# Ada_-_Sensor_-_issue_4_0.net
KiCad netlist of a schematic drawn in Altium Designer
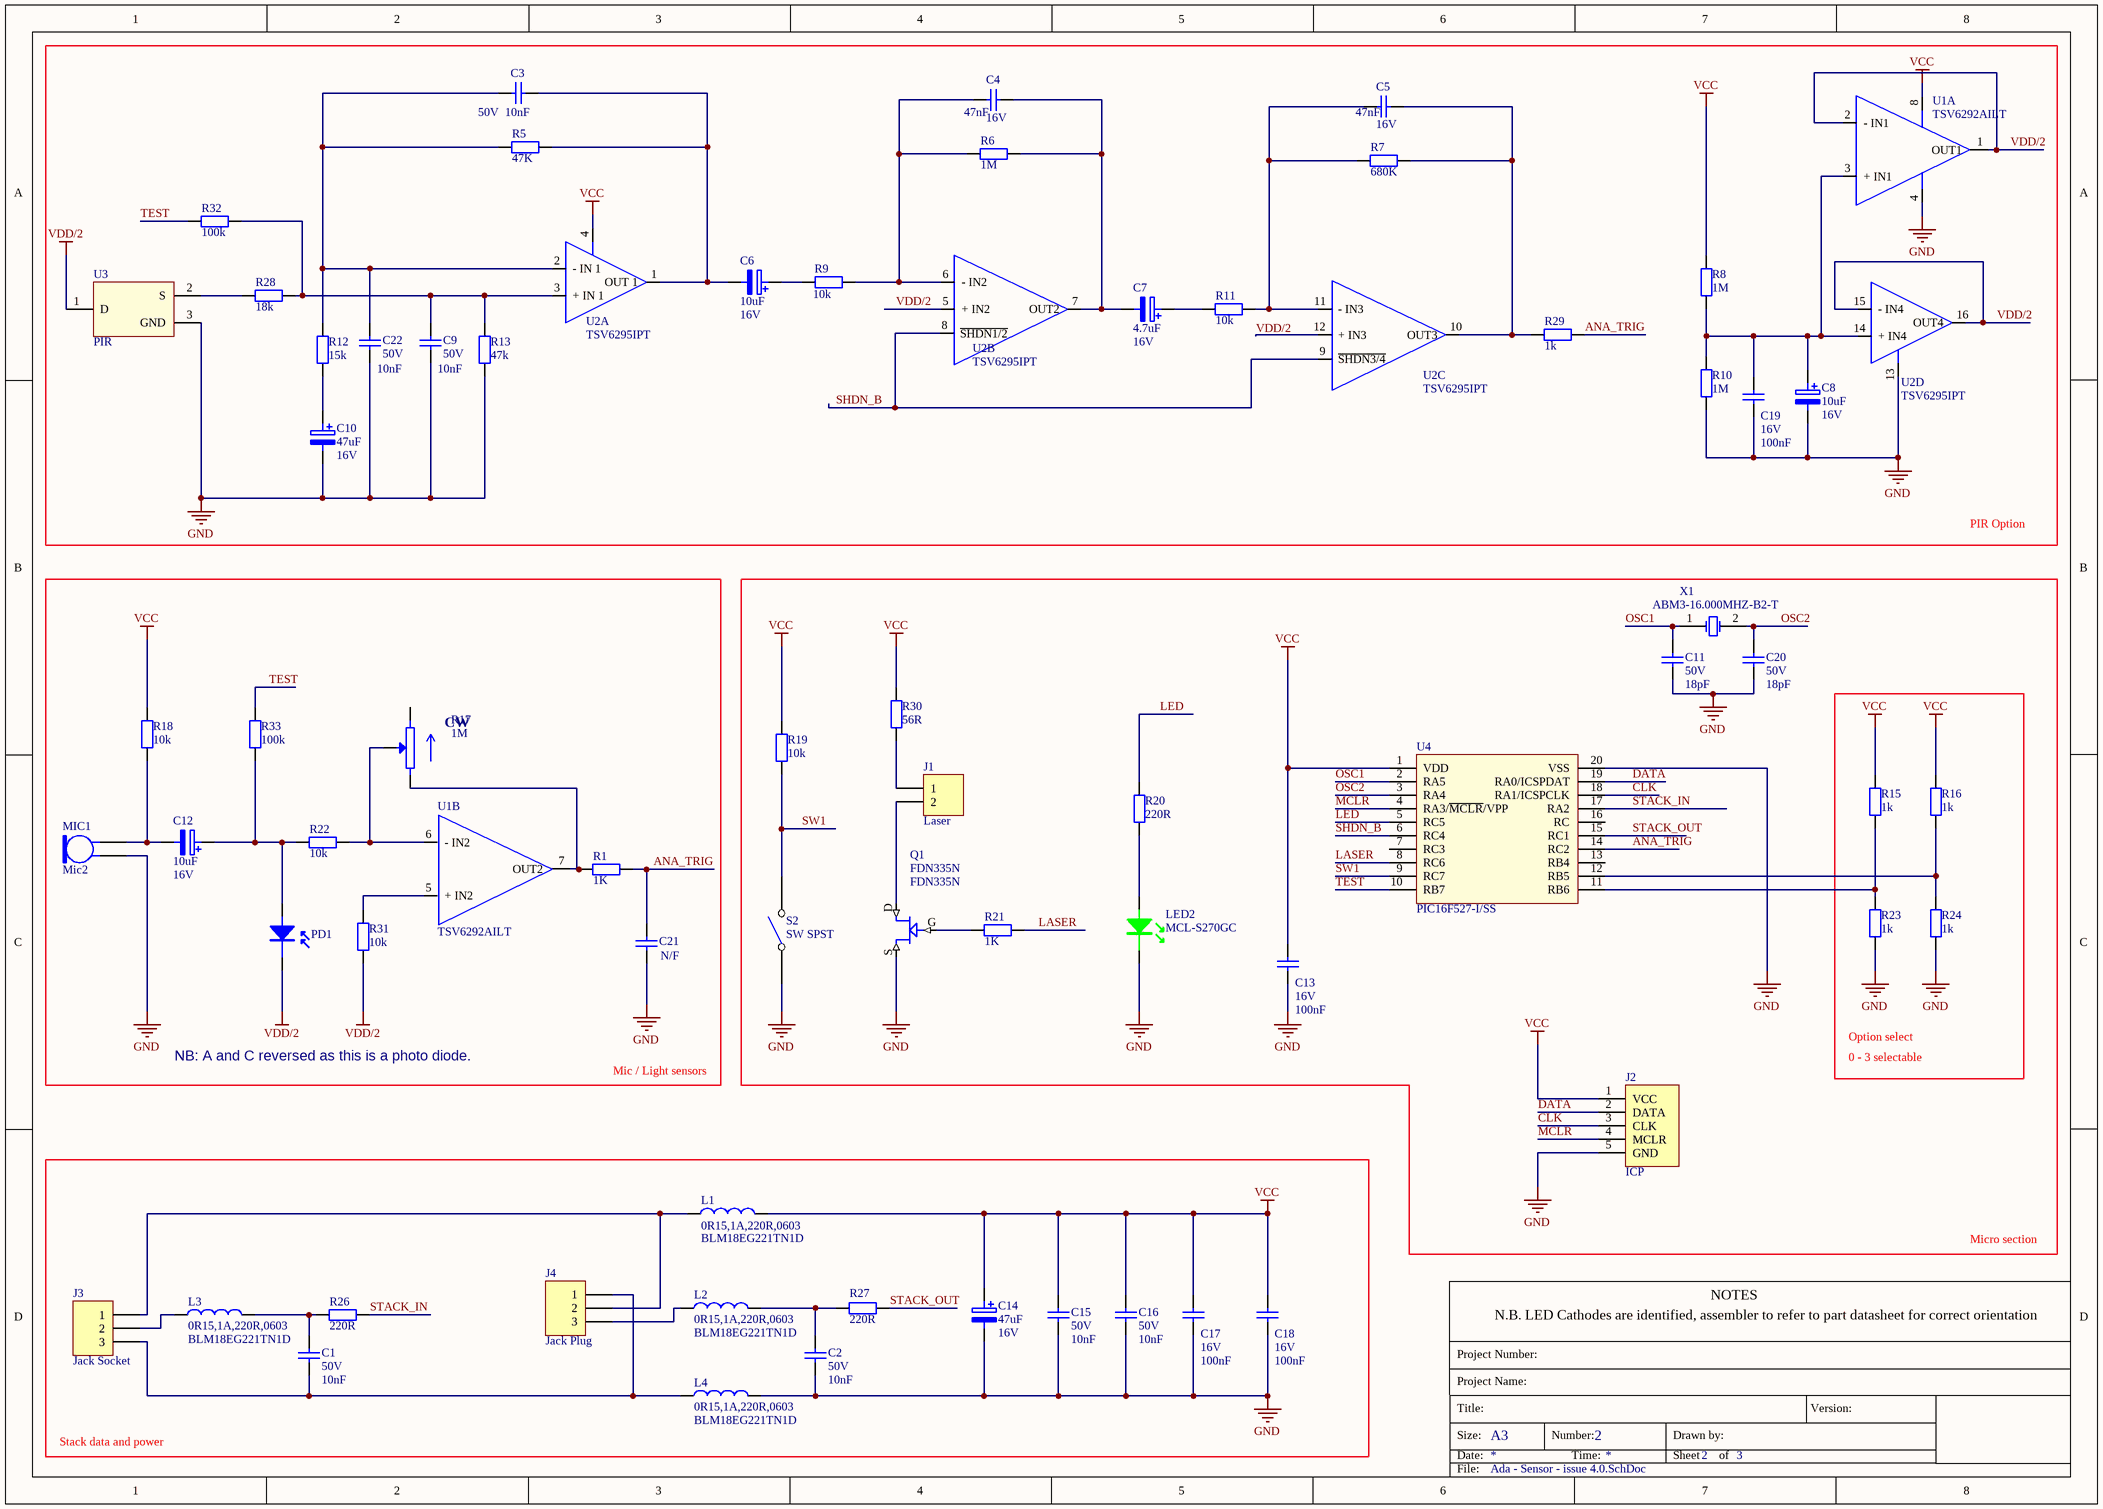
[diagram p0: Ada - Sensor - issue 4.0.SchDoc]

(export (version "E")
  (design (tool "Eeschema 10.0.6"))
  (components
    (comp (ref "C1")
      (value "10nF")
      (footprint "C0603")
      (description "Ceramic")
      (fields
        (field (name "MANUFACTURER") "MULTICOMP")
        (field (name "MANUF PART #") "MCCA000238")
        (field (name "VOLTAGE") "50V")
      )
      (libsource (lib "Capacitors") (part "10nF, 50V, 0603"))
    )
    (comp (ref "C2")
      (value "10nF")
      (footprint "C0603")
      (description "Ceramic")
      (fields
        (field (name "MANUFACTURER") "MULTICOMP")
        (field (name "MANUF PART #") "MCCA000238")
        (field (name "VOLTAGE") "50V")
      )
      (libsource (lib "Capacitors") (part "10nF, 50V, 0603"))
    )
    (comp (ref "C3")
      (value "10nF")
      (footprint "C0603")
      (description "Ceramic")
      (fields
        (field (name "MANUFACTURER") "MULTICOMP")
        (field (name "MANUF PART #") "MCCA000238")
        (field (name "VOLTAGE") "50V")
      )
      (libsource (lib "Passives Rev B") (part "Capacitor 0805"))
    )
    (comp (ref "C4")
      (value "47nF")
      (footprint "C0603")
      (description "Ceramic")
      (fields
        (field (name "MANUFACTURER") "YAGEO")
        (field (name "MANUF PART #") "CC0603KRX7R7BB473")
        (field (name "VOLTAGE") "16V")
      )
      (libsource (lib "Passives Rev B") (part "Capacitor 0603"))
    )
    (comp (ref "C5")
      (value "47nF")
      (footprint "C0603")
      (description "Ceramic")
      (fields
        (field (name "MANUFACTURER") "YAGEO")
        (field (name "MANUF PART #") "CC0603KRX7R7BB473")
        (field (name "VOLTAGE") "16V")
      )
      (libsource (lib "Passives Rev B") (part "Capacitor 0603"))
    )
    (comp (ref "C6")
      (value "10uF")
      (footprint "CASE_A")
      (description "ELECTROLYTIC")
      (fields
        (field (name "MANUFACTURER") "VISHAY SPRAGUE")
        (field (name "MANUF PART #") "293D106X9016A2TE3")
        (field (name "VOLTAGE") "16V")
      )
      (libsource (lib "Capacitors") (part "47uF, 25V, case D8"))
    )
    (comp (ref "C7")
      (value "4.7uF")
      (footprint "CASE_A")
      (description "TANT")
      (fields
        (field (name "MANUFACTURER") "VISHAY SPRAGUE")
        (field (name "MANUF PART #") "293D475X9016A2TE3")
        (field (name "VOLTAGE") "16V")
      )
      (libsource (lib "Capacitors") (part "47uF, 25V, case D8"))
    )
    (comp (ref "C8")
      (value "10uF")
      (footprint "CASE_A")
      (description "ELECTROLYTIC")
      (fields
        (field (name "MANUFACTURER") "VISHAY SPRAGUE")
        (field (name "MANUF PART #") "293D106X9016A2TE3")
        (field (name "VOLTAGE") "16V")
      )
      (libsource (lib "Capacitors") (part "47uF, 25V, case D8"))
    )
    (comp (ref "C9")
      (value "10nF")
      (footprint "C0603")
      (description "Ceramic")
      (fields
        (field (name "MANUFACTURER") "MULTICOMP")
        (field (name "MANUF PART #") "MCCA000238")
        (field (name "VOLTAGE") "50V")
      )
      (libsource (lib "Passives Rev B") (part "Capacitor 0805"))
    )
    (comp (ref "C10")
      (value "47uF")
      (footprint "CAP6.8/6.8")
      (description "ELECTROLYTIC")
      (fields
        (field (name "MANUFACTURER") "NICHICON")
        (field (name "MANUF PART #") "UUT1C470MCL1GS")
        (field (name "VOLTAGE") "16V")
      )
      (libsource (lib "Capacitors") (part "47uF, 25V, case D8"))
    )
    (comp (ref "C11")
      (value "18pF")
      (footprint "C0603")
      (description "Ceramic")
      (fields
        (field (name "MANUFACTURER") "KEMET")
        (field (name "MANUF PART #") "C0603C180J5GAC")
        (field (name "VOLTAGE") "50V")
      )
      (libsource (lib "Capacitors") (part "18pF, 50V, 0603"))
    )
    (comp (ref "C12")
      (value "10uF")
      (footprint "CASE_A")
      (description "ELECTROLYTIC")
      (fields
        (field (name "MANUFACTURER") "VISHAY SPRAGUE")
        (field (name "MANUF PART #") "293D106X9016A2TE3")
        (field (name "VOLTAGE") "16V")
      )
      (libsource (lib "Capacitors") (part "47uF, 25V, case D8"))
    )
    (comp (ref "C13")
      (value "100nF")
      (footprint "C0603")
      (description "Ceramic")
      (fields
        (field (name "MANUFACTURER") "TruCap")
        (field (name "MANUF PART #") "B0603R104")
        (field (name "VOLTAGE") "16V")
      )
      (libsource (lib "Capacitors") (part "100nF, 16V, 0603"))
    )
    (comp (ref "C14")
      (value "47uF")
      (footprint "CAP6.8/6.8")
      (description "ELECTROLYTIC")
      (fields
        (field (name "MANUFACTURER") "NICHICON")
        (field (name "MANUF PART #") "UUT1C470MCL1GS")
        (field (name "VOLTAGE") "16V")
      )
      (libsource (lib "Capacitors") (part "47uF, 25V, case D8"))
    )
    (comp (ref "C15")
      (value "10nF")
      (footprint "C0603")
      (description "Ceramic")
      (fields
        (field (name "MANUFACTURER") "MULTICOMP")
        (field (name "MANUF PART #") "MCCA000238")
        (field (name "VOLTAGE") "50V")
      )
      (libsource (lib "Capacitors") (part "10nF, 50V, 0603"))
    )
    (comp (ref "C16")
      (value "10nF")
      (footprint "C0603")
      (description "Ceramic")
      (fields
        (field (name "MANUFACTURER") "MULTICOMP")
        (field (name "MANUF PART #") "MCCA000238")
        (field (name "VOLTAGE") "50V")
      )
      (libsource (lib "Capacitors") (part "10nF, 50V, 0603"))
    )
    (comp (ref "C17")
      (value "100nF")
      (footprint "C0603")
      (description "Ceramic")
      (fields
        (field (name "MANUFACTURER") "TruCap")
        (field (name "MANUF PART #") "B0603R104")
        (field (name "VOLTAGE") "16V")
      )
      (libsource (lib "Capacitors") (part "100nF, 16V, 0603"))
    )
    (comp (ref "C18")
      (value "100nF")
      (footprint "C0603")
      (description "Ceramic")
      (fields
        (field (name "MANUFACTURER") "TruCap")
        (field (name "MANUF PART #") "B0603R104")
        (field (name "VOLTAGE") "16V")
      )
      (libsource (lib "Capacitors") (part "100nF, 16V, 0603"))
    )
    (comp (ref "C19")
      (value "100nF")
      (footprint "C0603")
      (description "Ceramic")
      (fields
        (field (name "MANUFACTURER") "TruCap")
        (field (name "MANUF PART #") "B0603R104")
        (field (name "VOLTAGE") "16V")
      )
      (libsource (lib "Capacitors") (part "100nF, 16V, 0603"))
    )
    (comp (ref "C20")
      (value "18pF")
      (footprint "C0603")
      (description "Ceramic")
      (fields
        (field (name "MANUFACTURER") "KEMET")
        (field (name "MANUF PART #") "C0603C180J5GAC")
        (field (name "VOLTAGE") "50V")
      )
      (libsource (lib "Capacitors") (part "18pF, 50V, 0603"))
    )
    (comp (ref "C21")
      (value "N/F")
      (footprint "C0603")
      (description "Ceramic")
      (fields (field (name "Comment") "Capacitor 0603"))
      (libsource (lib "Passives Rev B") (part "Capacitor 0603"))
    )
    (comp (ref "C22")
      (value "10nF")
      (footprint "C0603")
      (description "Ceramic")
      (fields
        (field (name "MANUFACTURER") "MULTICOMP")
        (field (name "MANUF PART #") "MCCA000238")
        (field (name "VOLTAGE") "50V")
      )
      (libsource (lib "Passives Rev B") (part "Capacitor 0805"))
    )
    (comp (ref "J1")
      (value "Laser")
      (footprint "SIP2")
      (description "Header, 2-Pin")
      (libsource (lib "Connectors") (part "Header 2"))
    )
    (comp (ref "J2")
      (value "ICP")
      (footprint "ICP")
      (description "PIC IN CIRCUIT PROGRAMMING HEADER")
      (fields (field (name "MANUFACTURER") "TruConnect") (field (name "MANUF PART #") "22-0510"))
      (libsource (lib "Connectors") (part "ICP"))
    )
    (comp (ref "J3")
      (value "Jack Socket")
      (footprint "sip3")
      (description "Header, 3-Pin")
      (libsource (lib "Connectors") (part "Header 3"))
    )
    (comp (ref "J4")
      (value "Jack Plug")
      (footprint "3 way sip RA")
      (description "Header, 3-Pin")
      (libsource (lib "Connectors") (part "Header 3"))
    )
    (comp (ref "L1")
      (value "0R15,1A,220R,0603")
      (footprint "L0603")
      (description "FERRITE BEAD")
      (fields
        (field (name "MANUFACTURER") "MURATA")
        (field (name "MANUF PART #") "BLM18EG221TN1D")
        (field (name "ALTIUM_VALUE") "BLM18EG221TN1D")
      )
      (libsource (lib "Inductors") (part "0R15,1A,220R,0603"))
    )
    (comp (ref "L2")
      (value "0R15,1A,220R,0603")
      (footprint "L0603")
      (description "FERRITE BEAD")
      (fields
        (field (name "MANUFACTURER") "MURATA")
        (field (name "MANUF PART #") "BLM18EG221TN1D")
        (field (name "ALTIUM_VALUE") "BLM18EG221TN1D")
      )
      (libsource (lib "Inductors") (part "0R15,1A,220R,0603"))
    )
    (comp (ref "L3")
      (value "0R15,1A,220R,0603")
      (footprint "L0603")
      (description "FERRITE BEAD")
      (fields
        (field (name "MANUFACTURER") "MURATA")
        (field (name "MANUF PART #") "BLM18EG221TN1D")
        (field (name "ALTIUM_VALUE") "BLM18EG221TN1D")
      )
      (libsource (lib "Inductors") (part "0R15,1A,220R,0603"))
    )
    (comp (ref "L4")
      (value "0R15,1A,220R,0603")
      (footprint "L0603")
      (description "FERRITE BEAD")
      (fields
        (field (name "MANUFACTURER") "MURATA")
        (field (name "MANUF PART #") "BLM18EG221TN1D")
        (field (name "ALTIUM_VALUE") "BLM18EG221TN1D")
      )
      (libsource (lib "Inductors") (part "0R15,1A,220R,0603"))
    )
    (comp (ref "LED2")
      (value "MCL-S270GC")
      (footprint "LED, GREEN, 0805")
      (description "MULTICOMP")
      (fields (field (name "PART NO.") "1581242") (field (name "Comment") "LED GREEN 0805"))
      (libsource (lib "Diodes") (part "LED GREEN 0805"))
    )
    (comp (ref "MIC1")
      (value "Mic2")
      (footprint "ECM")
      (description "PROJECTS UNLIMITED - AOM-4542P-R - MICROPHONE, OMNI PCB, 9.7MM")
      (fields (field (name "MANUFACTURER") "PROJECTS UNLIMITED") (field (name "MANUF PART #") "AOM-4542P-R"))
      (libsource (lib "General") (part "Mic2"))
    )
    (comp (ref "PD1")
      (value "PHOTODIODE")
      (footprint "DOME LENS")
      (description "DIODE, PIN, SMD, DOME LENS")
      (fields (field (name "MANUFACTURER") "VISHAY") (field (name "MANUF PART #") "VEMD2520X01"))
      (libsource (lib "ECO001_LIB") (part "PHOTODIODE"))
    )
    (comp (ref "Q1")
      (value "FDN335N")
      (footprint "SOT-23")
      (fields
        (field (name "MANUFACTURER") "FAIRCHILD SEMICONDUCTOR")
        (field (name "PART NO.") "9845348RL")
        (field (name "ALTIUM_VALUE") "FDN335N")
      )
      (libsource (lib "Transistors and FETs") (part "FDN335N"))
    )
    (comp (ref "R1")
      (value "1K")
      (footprint "R0603")
      (description "Resistor 0603")
      (libsource (lib "") (part "Resistor 0603_3"))
    )
    (comp (ref "R5")
      (value "47K")
      (footprint "R0603")
      (description "Resistor 0603")
      (libsource (lib "") (part "Resistor 0603_1"))
    )
    (comp (ref "R6")
      (value "1M")
      (footprint "R0603")
      (description "Resistor 0603")
      (libsource (lib "") (part "Resistor 0603_3"))
    )
    (comp (ref "R7")
      (value "680K")
      (footprint "R0603")
      (description "Resistor 0603")
      (libsource (lib "") (part "Resistor 0603_1"))
    )
    (comp (ref "R8")
      (value "1M")
      (footprint "R0603")
      (description "Resistor 0603")
      (libsource (lib "") (part "Resistor 0603_2"))
    )
    (comp (ref "R9")
      (value "10k")
      (footprint "R0603")
      (description "Resistor 0603")
      (libsource (lib "") (part "Resistor 0603_1"))
    )
    (comp (ref "R10")
      (value "1M")
      (footprint "R0603")
      (description "Resistor 0603")
      (libsource (lib "") (part "Resistor 0603_2"))
    )
    (comp (ref "R11")
      (value "10k")
      (footprint "R0603")
      (description "Resistor 0603")
      (libsource (lib "") (part "Resistor 0603_1"))
    )
    (comp (ref "R12")
      (value "15k")
      (footprint "R0603")
      (description "Resistor 0603")
      (libsource (lib "") (part "Resistor 0603_2"))
    )
    (comp (ref "R13")
      (value "47k")
      (footprint "R0603")
      (description "Resistor 0805")
      (libsource (lib "Passives Rev B") (part "Resistor 0805"))
    )
    (comp (ref "R15")
      (value "1k")
      (footprint "R0603")
      (description "Resistor 0603")
      (libsource (lib "") (part "Resistor 0603_2"))
    )
    (comp (ref "R16")
      (value "1k")
      (footprint "R0603")
      (description "Resistor 0603")
      (libsource (lib "") (part "Resistor 0603_2"))
    )
    (comp (ref "R17")
      (value "1M")
      (footprint "preset_Iskra square")
      (description "1m Pnz10za Preset Potentiometer")
      (fields (field (name "MANUFACTURER") "Iskra") (field (name "MANUF PART #") "PNZ10ZA 1M"))
      (libsource (lib "DEVICE") (part "POT2"))
    )
    (comp (ref "R18")
      (value "10k")
      (footprint "R0603")
      (description "Resistor 0603")
      (libsource (lib "") (part "Resistor 0603_3"))
    )
    (comp (ref "R19")
      (value "10k")
      (footprint "R0603")
      (description "Resistor 0603")
      (libsource (lib "") (part "Resistor 0603_2"))
    )
    (comp (ref "R20")
      (value "220R")
      (footprint "R0603")
      (description "Resistor 0603")
      (libsource (lib "") (part "Resistor 0603_2"))
    )
    (comp (ref "R21")
      (value "1K")
      (footprint "R0603")
      (description "Resistor 0603")
      (libsource (lib "") (part "Resistor 0603_1"))
    )
    (comp (ref "R22")
      (value "10k")
      (footprint "R0603")
      (description "Resistor 0603")
      (libsource (lib "Passives Rev B") (part "Resistor 0603"))
    )
    (comp (ref "R23")
      (value "1k")
      (footprint "R0603")
      (description "Resistor 0603")
      (libsource (lib "") (part "Resistor 0603_2"))
    )
    (comp (ref "R24")
      (value "1k")
      (footprint "R0603")
      (description "Resistor 0603")
      (libsource (lib "") (part "Resistor 0603_2"))
    )
    (comp (ref "R26")
      (value "220R")
      (footprint "R0603")
      (description "Resistor 0603")
      (libsource (lib "Passives Rev B") (part "Resistor 0603"))
    )
    (comp (ref "R27")
      (value "220R")
      (footprint "R0603")
      (description "Resistor 0603")
      (libsource (lib "Passives Rev B") (part "Resistor 0603"))
    )
    (comp (ref "R28")
      (value "18k")
      (footprint "R0603")
      (description "Resistor 0603")
      (libsource (lib "") (part "Resistor 0603_1"))
    )
    (comp (ref "R29")
      (value "1k")
      (footprint "R0603")
      (description "Resistor 0603")
      (libsource (lib "") (part "Resistor 0603_1"))
    )
    (comp (ref "R30")
      (value "56R")
      (footprint "R0603")
      (description "Resistor 0603")
      (libsource (lib "") (part "Resistor 0603_2"))
    )
    (comp (ref "R31")
      (value "10k")
      (footprint "R0603")
      (description "Resistor 0603")
      (libsource (lib "") (part "Resistor 0603_1"))
    )
    (comp (ref "R32")
      (value "100k")
      (footprint "R0603")
      (description "Resistor 0603")
      (libsource (lib "") (part "Resistor 0603_1"))
    )
    (comp (ref "R33")
      (value "100k")
      (footprint "R0603")
      (description "Resistor 0603")
      (libsource (lib "Passives Rev B") (part "Resistor 0603"))
    )
    (comp (ref "S2")
      (value "SW SPST")
      (footprint "MFP113D")
      (fields
        (field (name "MANUFACTURER") "KNITTER-SWITCH")
        (field (name "MANUF PART #") "MFP113D")
        (field (name "PART NO.") "702-3634")
      )
      (libsource (lib "Switches") (part "SW SPST"))
    )
    (comp (ref "U1")
      (value "TSV6292AILT")
      (footprint "SOT23 8 pin")
      (description "low power Op Amp")
      (fields (field (name "MANUFACTURER") "STMICROELECTRONICS") (field (name "PART NO.") "2067873"))
      (libsource (lib "TRI002_SCHLIB_1.3") (part "TSV6292AILT"))
    )
    (comp (ref "U2")
      (value "TSV6295IPT")
      (footprint "TSSOP16")
      (description "low power Op Amp")
      (fields (field (name "MANUFACTURER") "STMICROELECTRONICS") (field (name "PART NO.") "1842580"))
      (libsource (lib "ECO001_LIB") (part "TSV6295IPT"))
    )
    (comp (ref "U3")
      (value "PIR")
      (footprint "PIR_TO-5")
      (description "PIR detector")
      (fields (field (name "MANUFACTURER") "EXCELITAS TECH") (field (name "MANUF PART #") "LHI_968"))
      (libsource (lib "ECO001_LIB") (part "LHI_968"))
    )
    (comp (ref "U4")
      (value "PIC16F527-I/SS")
      (footprint "SSOP20")
      (description "8bit uProcessor")
      (fields (field (name "MANUFACTURER") "MICROCHIP") (field (name "PART NO.") "2301100"))
      (libsource (lib "TRI002 Sensor") (part "PIC16F527"))
    )
    (comp (ref "X1")
      (value "ABM3-16.000MHZ-B2-T")
      (footprint "ABS10")
      (description "CRYSTAL, 16MHZ, 18PF CL, 5X3.2MM, SMT")
      (fields (field (name "MANUFACTURER") "ABRACON") (field (name "PART NO.") "1611806"))
      (libsource (lib "General") (part "XTAL SMD 2pin"))
    )
  )
  (nets
    (net (code "1") (name "/ANA_TRIG") (class "Default")
      (node (ref "C21") (pin "2") (pinfunction "2_2") (pintype "passive"))
      (node (ref "R1") (pin "2") (pinfunction "2_2") (pintype "passive"))
      (node (ref "R29") (pin "1") (pinfunction "1_1") (pintype "passive"))
      (node (ref "U4") (pin "14") (pinfunction "RC2_14") (pintype "passive"))
    )
    (net (code "2") (name "/CLK") (class "Default")
      (node (ref "J2") (pin "3") (pinfunction "CLK_3") (pintype "passive"))
      (node (ref "U4") (pin "18") (pinfunction "RA1/ICSPCLK_18") (pintype "passive"))
    )
    (net (code "3") (name "/DATA") (class "Default")
      (node (ref "J2") (pin "2") (pinfunction "DATA_2") (pintype "passive"))
      (node (ref "U4") (pin "19") (pinfunction "RA0/ICSPDAT_19") (pintype "passive"))
    )
    (net (code "4") (name "/LASER") (class "Default")
      (node (ref "R21") (pin "1") (pinfunction "1_1") (pintype "passive"))
      (node (ref "U4") (pin "8") (pinfunction "RC6_8") (pintype "passive"))
    )
    (net (code "5") (name "/LED") (class "Default")
      (node (ref "R20") (pin "2") (pinfunction "2_2") (pintype "passive"))
      (node (ref "U4") (pin "5") (pinfunction "RC5_5") (pintype "passive"))
    )
    (net (code "6") (name "/MCLR") (class "Default")
      (node (ref "J2") (pin "4") (pinfunction "MCLR_4") (pintype "passive"))
      (node (ref "U4") (pin "4") (pinfunction "RA3/~{MCLR}/VPP_4") (pintype "passive"))
    )
    (net (code "7") (name "/OSC1") (class "Default")
      (node (ref "C11") (pin "2") (pinfunction "2_2") (pintype "passive"))
      (node (ref "U4") (pin "2") (pinfunction "RA5_2") (pintype "passive"))
      (node (ref "X1") (pin "1") (pinfunction "OSC1_1") (pintype "passive"))
    )
    (net (code "8") (name "/OSC2") (class "Default")
      (node (ref "C20") (pin "2") (pinfunction "2_2") (pintype "passive"))
      (node (ref "U4") (pin "3") (pinfunction "RA4_3") (pintype "passive"))
      (node (ref "X1") (pin "2") (pinfunction "OSC2_2") (pintype "passive"))
    )
    (net (code "9") (name "/SHDN_B") (class "Default")
      (node (ref "U2") (pin "8") (pinfunction "~{SHDN1/2}_8") (pintype "passive"))
      (node (ref "U2") (pin "9") (pinfunction "~{SHDN3/4}_9") (pintype "passive"))
      (node (ref "U4") (pin "6") (pinfunction "RC4_6") (pintype "passive"))
    )
    (net (code "10") (name "/STACK_IN") (class "Default")
      (node (ref "R26") (pin "1") (pinfunction "1_1") (pintype "passive"))
      (node (ref "U4") (pin "17") (pinfunction "RA2_17") (pintype "passive"))
    )
    (net (code "11") (name "/STACK_OUT") (class "Default")
      (node (ref "R27") (pin "1") (pinfunction "1_1") (pintype "passive"))
      (node (ref "U4") (pin "15") (pinfunction "RC1_15") (pintype "passive"))
    )
    (net (code "12") (name "/SW1") (class "Default")
      (node (ref "R19") (pin "1") (pinfunction "1_1") (pintype "passive"))
      (node (ref "S2") (pin "2") (pinfunction "NO_2") (pintype "passive"))
      (node (ref "U4") (pin "9") (pinfunction "RC7_9") (pintype "passive"))
    )
    (net (code "13") (name "/TEST") (class "Default")
      (node (ref "R32") (pin "2") (pinfunction "2_2") (pintype "passive"))
      (node (ref "R33") (pin "1") (pinfunction "1_1") (pintype "passive"))
      (node (ref "U4") (pin "10") (pinfunction "RB7_10") (pintype "passive"))
    )
    (net (code "14") (name "GND") (class "Default")
      (node (ref "C10") (pin "2") (pinfunction "2_2") (pintype "passive"))
      (node (ref "C11") (pin "1") (pinfunction "1_1") (pintype "passive"))
      (node (ref "C13") (pin "1") (pinfunction "1_1") (pintype "passive"))
      (node (ref "C14") (pin "2") (pinfunction "2_2") (pintype "passive"))
      (node (ref "C15") (pin "1") (pinfunction "1_1") (pintype "passive"))
      (node (ref "C16") (pin "1") (pinfunction "1_1") (pintype "passive"))
      (node (ref "C17") (pin "1") (pinfunction "1_1") (pintype "passive"))
      (node (ref "C18") (pin "1") (pinfunction "1_1") (pintype "passive"))
      (node (ref "C19") (pin "1") (pinfunction "1_1") (pintype "passive"))
      (node (ref "C2") (pin "1") (pinfunction "1_1") (pintype "passive"))
      (node (ref "C20") (pin "1") (pinfunction "1_1") (pintype "passive"))
      (node (ref "C21") (pin "1") (pinfunction "1_1") (pintype "passive"))
      (node (ref "C22") (pin "1") (pinfunction "1_1") (pintype "passive"))
      (node (ref "C8") (pin "2") (pinfunction "2_2") (pintype "passive"))
      (node (ref "C9") (pin "1") (pinfunction "1_1") (pintype "passive"))
      (node (ref "J2") (pin "5") (pinfunction "GND_5") (pintype "passive"))
      (node (ref "L4") (pin "2") (pinfunction "2_2") (pintype "passive"))
      (node (ref "LED2") (pin "K") (pinfunction "K_K") (pintype "passive"))
      (node (ref "MIC1") (pin "2") (pinfunction "2_2") (pintype "passive"))
      (node (ref "Q1") (pin "S") (pinfunction "S_S") (pintype "input"))
      (node (ref "R10") (pin "1") (pinfunction "1_1") (pintype "passive"))
      (node (ref "R13") (pin "2") (pinfunction "2_2") (pintype "passive"))
      (node (ref "R23") (pin "1") (pinfunction "1_1") (pintype "passive"))
      (node (ref "R24") (pin "1") (pinfunction "1_1") (pintype "passive"))
      (node (ref "S2") (pin "1") (pinfunction "COMMON_1") (pintype "passive"))
      (node (ref "U1") (pin "4") (pinfunction "V+_4") (pintype "passive"))
      (node (ref "U2") (pin "13") (pinfunction "V-_13") (pintype "passive"))
      (node (ref "U3") (pin "3") (pinfunction "GND_3") (pintype "passive"))
      (node (ref "U4") (pin "20") (pinfunction "VSS_20") (pintype "passive"))
    )
    (net (code "15") (name "Net-(C1-Pad1)") (class "Default")
      (node (ref "C1") (pin "1") (pinfunction "1_1") (pintype "passive"))
      (node (ref "J3") (pin "3") (pinfunction "3_3") (pintype "passive"))
      (node (ref "J4") (pin "1") (pinfunction "1_1") (pintype "passive"))
      (node (ref "L4") (pin "1") (pinfunction "1_1") (pintype "passive"))
    )
    (net (code "16") (name "Net-(C1-Pad2)") (class "Default")
      (node (ref "C1") (pin "2") (pinfunction "2_2") (pintype "passive"))
      (node (ref "L3") (pin "2") (pinfunction "2_2") (pintype "passive"))
      (node (ref "R26") (pin "2") (pinfunction "2_2") (pintype "passive"))
    )
    (net (code "17") (name "Net-(C2-Pad2)") (class "Default")
      (node (ref "C2") (pin "2") (pinfunction "2_2") (pintype "passive"))
      (node (ref "L2") (pin "2") (pinfunction "2_2") (pintype "passive"))
      (node (ref "R27") (pin "2") (pinfunction "2_2") (pintype "passive"))
    )
    (net (code "18") (name "Net-(C6-Pad1)") (class "Default")
      (node (ref "C6") (pin "1") (pinfunction "1_1") (pintype "passive"))
      (node (ref "R9") (pin "2") (pinfunction "2_2") (pintype "passive"))
    )
    (net (code "19") (name "Net-(C7-Pad1)") (class "Default")
      (node (ref "C7") (pin "1") (pinfunction "1_1") (pintype "passive"))
      (node (ref "R11") (pin "2") (pinfunction "2_2") (pintype "passive"))
    )
    (net (code "20") (name "Net-(C10-Pad1)") (class "Default")
      (node (ref "C10") (pin "1") (pinfunction "1_1") (pintype "passive"))
      (node (ref "R12") (pin "1") (pinfunction "1_1") (pintype "passive"))
    )
    (net (code "21") (name "Net-(C12-Pad1)") (class "Default")
      (node (ref "C12") (pin "1") (pinfunction "1_1") (pintype "passive"))
      (node (ref "PD1") (pin "A") (pinfunction "A_A") (pintype "passive"))
      (node (ref "R22") (pin "2") (pinfunction "2_2") (pintype "passive"))
      (node (ref "R33") (pin "2") (pinfunction "2_2") (pintype "passive"))
    )
    (net (code "22") (name "Net-(C12-Pad2)") (class "Default")
      (node (ref "C12") (pin "2") (pinfunction "2_2") (pintype "passive"))
      (node (ref "MIC1") (pin "1") (pinfunction "1_1") (pintype "passive"))
      (node (ref "R18") (pin "1") (pinfunction "1_1") (pintype "passive"))
    )
    (net (code "23") (name "Net-(J1-Pad1)") (class "Default")
      (node (ref "J1") (pin "1") (pinfunction "1_1") (pintype "passive"))
      (node (ref "R30") (pin "1") (pinfunction "1_1") (pintype "passive"))
    )
    (net (code "24") (name "Net-(J1-Pad2)") (class "Default")
      (node (ref "J1") (pin "2") (pinfunction "2_2") (pintype "passive"))
      (node (ref "Q1") (pin "D") (pinfunction "D_D") (pintype "input"))
    )
    (net (code "25") (name "Net-(J3-Pad1)") (class "Default")
      (node (ref "J3") (pin "1") (pinfunction "1_1") (pintype "passive"))
      (node (ref "J4") (pin "2") (pinfunction "2_2") (pintype "passive"))
      (node (ref "L1") (pin "1") (pinfunction "1_1") (pintype "passive"))
    )
    (net (code "26") (name "Net-(J3-Pad2)") (class "Default")
      (node (ref "J3") (pin "2") (pinfunction "2_2") (pintype "passive"))
      (node (ref "L3") (pin "1") (pinfunction "1_1") (pintype "passive"))
    )
    (net (code "27") (name "Net-(J4-Pad3)") (class "Default")
      (node (ref "J4") (pin "3") (pinfunction "3_3") (pintype "passive"))
      (node (ref "L2") (pin "1") (pinfunction "1_1") (pintype "passive"))
    )
    (net (code "28") (name "Net-(LED2-PadA)") (class "Default")
      (node (ref "LED2") (pin "A") (pinfunction "A_A") (pintype "passive"))
      (node (ref "R20") (pin "1") (pinfunction "1_1") (pintype "passive"))
    )
    (net (code "29") (name "Net-(Q1-PadG)") (class "Default")
      (node (ref "Q1") (pin "G") (pinfunction "G_G") (pintype "input"))
      (node (ref "R21") (pin "2") (pinfunction "2_2") (pintype "passive"))
    )
    (net (code "30") (name "Net-(U1A-+_IN1)") (class "Default")
      (node (ref "C19") (pin "2") (pinfunction "2_2") (pintype "passive"))
      (node (ref "C8") (pin "1") (pinfunction "1_1") (pintype "passive"))
      (node (ref "R10") (pin "2") (pinfunction "2_2") (pintype "passive"))
      (node (ref "R8") (pin "1") (pinfunction "1_1") (pintype "passive"))
      (node (ref "U1") (pin "3") (pinfunction "+_IN1_3") (pintype "passive"))
      (node (ref "U2") (pin "14") (pinfunction "+_IN4_14") (pintype "passive"))
    )
    (net (code "31") (name "Net-(U1B-+_IN2)") (class "Default")
      (node (ref "R31") (pin "1") (pinfunction "1_1") (pintype "passive"))
      (node (ref "U1") (pin "5") (pinfunction "+_IN2_5") (pintype "passive"))
    )
    (net (code "32") (name "Net-(U1B--_IN2)") (class "Default")
      (node (ref "R17") (pin "W") (pintype "passive"))
      (node (ref "R22") (pin "1") (pinfunction "1_1") (pintype "passive"))
      (node (ref "U1") (pin "6") (pinfunction "-_IN2_6") (pintype "passive"))
    )
    (net (code "33") (name "Net-(U1B-OUT2)") (class "Default")
      (node (ref "R1") (pin "1") (pinfunction "1_1") (pintype "passive"))
      (node (ref "R17") (pin "2") (pintype "passive"))
      (node (ref "U1") (pin "7") (pinfunction "OUT2_7") (pintype "passive"))
    )
    (net (code "34") (name "Net-(U2A-+_IN_1)") (class "Default")
      (node (ref "C9") (pin "2") (pinfunction "2_2") (pintype "passive"))
      (node (ref "R13") (pin "1") (pinfunction "1_1") (pintype "passive"))
      (node (ref "R28") (pin "1") (pinfunction "1_1") (pintype "passive"))
      (node (ref "R32") (pin "1") (pinfunction "1_1") (pintype "passive"))
      (node (ref "U2") (pin "3") (pinfunction "+_IN_1_3") (pintype "passive"))
    )
    (net (code "35") (name "Net-(U2A--_IN_1)") (class "Default")
      (node (ref "C22") (pin "2") (pinfunction "2_2") (pintype "passive"))
      (node (ref "C3") (pin "2") (pinfunction "2_2") (pintype "passive"))
      (node (ref "R12") (pin "2") (pinfunction "2_2") (pintype "passive"))
      (node (ref "R5") (pin "2") (pinfunction "2_2") (pintype "passive"))
      (node (ref "U2") (pin "2") (pinfunction "-_IN_1_2") (pintype "passive"))
    )
    (net (code "36") (name "Net-(U2A-OUT_1)") (class "Default")
      (node (ref "C3") (pin "1") (pinfunction "1_1") (pintype "passive"))
      (node (ref "C6") (pin "2") (pinfunction "2_2") (pintype "passive"))
      (node (ref "R5") (pin "1") (pinfunction "1_1") (pintype "passive"))
      (node (ref "U2") (pin "1") (pinfunction "OUT_1_1") (pintype "passive"))
    )
    (net (code "37") (name "Net-(U2B--_IN2)") (class "Default")
      (node (ref "C4") (pin "2") (pinfunction "2_2") (pintype "passive"))
      (node (ref "R6") (pin "1") (pinfunction "1_1") (pintype "passive"))
      (node (ref "R9") (pin "1") (pinfunction "1_1") (pintype "passive"))
      (node (ref "U2") (pin "6") (pinfunction "-_IN2_6") (pintype "passive"))
    )
    (net (code "38") (name "Net-(U2B-OUT2)") (class "Default")
      (node (ref "C4") (pin "1") (pinfunction "1_1") (pintype "passive"))
      (node (ref "C7") (pin "2") (pinfunction "2_2") (pintype "passive"))
      (node (ref "R6") (pin "2") (pinfunction "2_2") (pintype "passive"))
      (node (ref "U2") (pin "7") (pinfunction "OUT2_7") (pintype "passive"))
    )
    (net (code "39") (name "Net-(U2C--_IN3)") (class "Default")
      (node (ref "C5") (pin "2") (pinfunction "2_2") (pintype "passive"))
      (node (ref "R11") (pin "1") (pinfunction "1_1") (pintype "passive"))
      (node (ref "R7") (pin "2") (pinfunction "2_2") (pintype "passive"))
      (node (ref "U2") (pin "11") (pinfunction "-_IN3_11") (pintype "passive"))
    )
    (net (code "40") (name "Net-(U2C-OUT3)") (class "Default")
      (node (ref "C5") (pin "1") (pinfunction "1_1") (pintype "passive"))
      (node (ref "R29") (pin "2") (pinfunction "2_2") (pintype "passive"))
      (node (ref "R7") (pin "1") (pinfunction "1_1") (pintype "passive"))
      (node (ref "U2") (pin "10") (pinfunction "OUT3_10") (pintype "passive"))
    )
    (net (code "41") (name "Net-(U3-S)") (class "Default")
      (node (ref "R28") (pin "2") (pinfunction "2_2") (pintype "passive"))
      (node (ref "U3") (pin "2") (pinfunction "S_2") (pintype "passive"))
    )
    (net (code "42") (name "Net-(U4-RB5)") (class "Default")
      (node (ref "R16") (pin "1") (pinfunction "1_1") (pintype "passive"))
      (node (ref "R24") (pin "2") (pinfunction "2_2") (pintype "passive"))
      (node (ref "U4") (pin "12") (pinfunction "RB5_12") (pintype "passive"))
    )
    (net (code "43") (name "Net-(U4-RB6)") (class "Default")
      (node (ref "R15") (pin "1") (pinfunction "1_1") (pintype "passive"))
      (node (ref "R23") (pin "2") (pinfunction "2_2") (pintype "passive"))
      (node (ref "U4") (pin "11") (pinfunction "RB6_11") (pintype "passive"))
    )
    (net (code "44") (name "VCC") (class "Default")
      (node (ref "C13") (pin "2") (pinfunction "2_2") (pintype "passive"))
      (node (ref "C14") (pin "1") (pinfunction "1_1") (pintype "passive"))
      (node (ref "C15") (pin "2") (pinfunction "2_2") (pintype "passive"))
      (node (ref "C16") (pin "2") (pinfunction "2_2") (pintype "passive"))
      (node (ref "C17") (pin "2") (pinfunction "2_2") (pintype "passive"))
      (node (ref "C18") (pin "2") (pinfunction "2_2") (pintype "passive"))
      (node (ref "J2") (pin "1") (pinfunction "VCC_1") (pintype "passive"))
      (node (ref "L1") (pin "2") (pinfunction "2_2") (pintype "passive"))
      (node (ref "R15") (pin "2") (pinfunction "2_2") (pintype "passive"))
      (node (ref "R16") (pin "2") (pinfunction "2_2") (pintype "passive"))
      (node (ref "R18") (pin "2") (pinfunction "2_2") (pintype "passive"))
      (node (ref "R19") (pin "2") (pinfunction "2_2") (pintype "passive"))
      (node (ref "R30") (pin "2") (pinfunction "2_2") (pintype "passive"))
      (node (ref "R8") (pin "2") (pinfunction "2_2") (pintype "passive"))
      (node (ref "U1") (pin "8") (pinfunction "V+_8") (pintype "passive"))
      (node (ref "U2") (pin "4") (pinfunction "V+_4") (pintype "passive"))
      (node (ref "U4") (pin "1") (pinfunction "VDD_1") (pintype "passive"))
    )
    (net (code "45") (name "VDD{slash}2") (class "Default")
      (node (ref "PD1") (pin "K") (pinfunction "K_K") (pintype "passive"))
      (node (ref "R31") (pin "2") (pinfunction "2_2") (pintype "passive"))
      (node (ref "U1") (pin "1") (pinfunction "OUT1_1") (pintype "passive"))
      (node (ref "U1") (pin "2") (pinfunction "-_IN1_2") (pintype "passive"))
      (node (ref "U2") (pin "12") (pinfunction "+_IN3_12") (pintype "passive"))
      (node (ref "U2") (pin "15") (pinfunction "-_IN4_15") (pintype "passive"))
      (node (ref "U2") (pin "16") (pinfunction "OUT4_16") (pintype "passive"))
      (node (ref "U2") (pin "5") (pinfunction "+_IN2_5") (pintype "passive"))
      (node (ref "U3") (pin "1") (pinfunction "D_1") (pintype "passive"))
    )
    (net (code "46") (name "unconnected-(R17-Pad1)") (class "Default")
      (node (ref "R17") (pin "1") (pintype "passive"))
    )
    (net (code "47") (name "unconnected-(U4-RB4-Pad13)") (class "Default")
      (node (ref "U4") (pin "13") (pinfunction "RB4_13") (pintype "passive"))
    )
    (net (code "48") (name "unconnected-(U4-RC-Pad16)") (class "Default")
      (node (ref "U4") (pin "16") (pinfunction "RC_16") (pintype "passive"))
    )
    (net (code "49") (name "unconnected-(U4-RC3-Pad7)") (class "Default")
      (node (ref "U4") (pin "7") (pinfunction "RC3_7") (pintype "passive"))
    )
  )
)
